# Main.net
KiCad netlist of a schematic drawn in Altium Designer
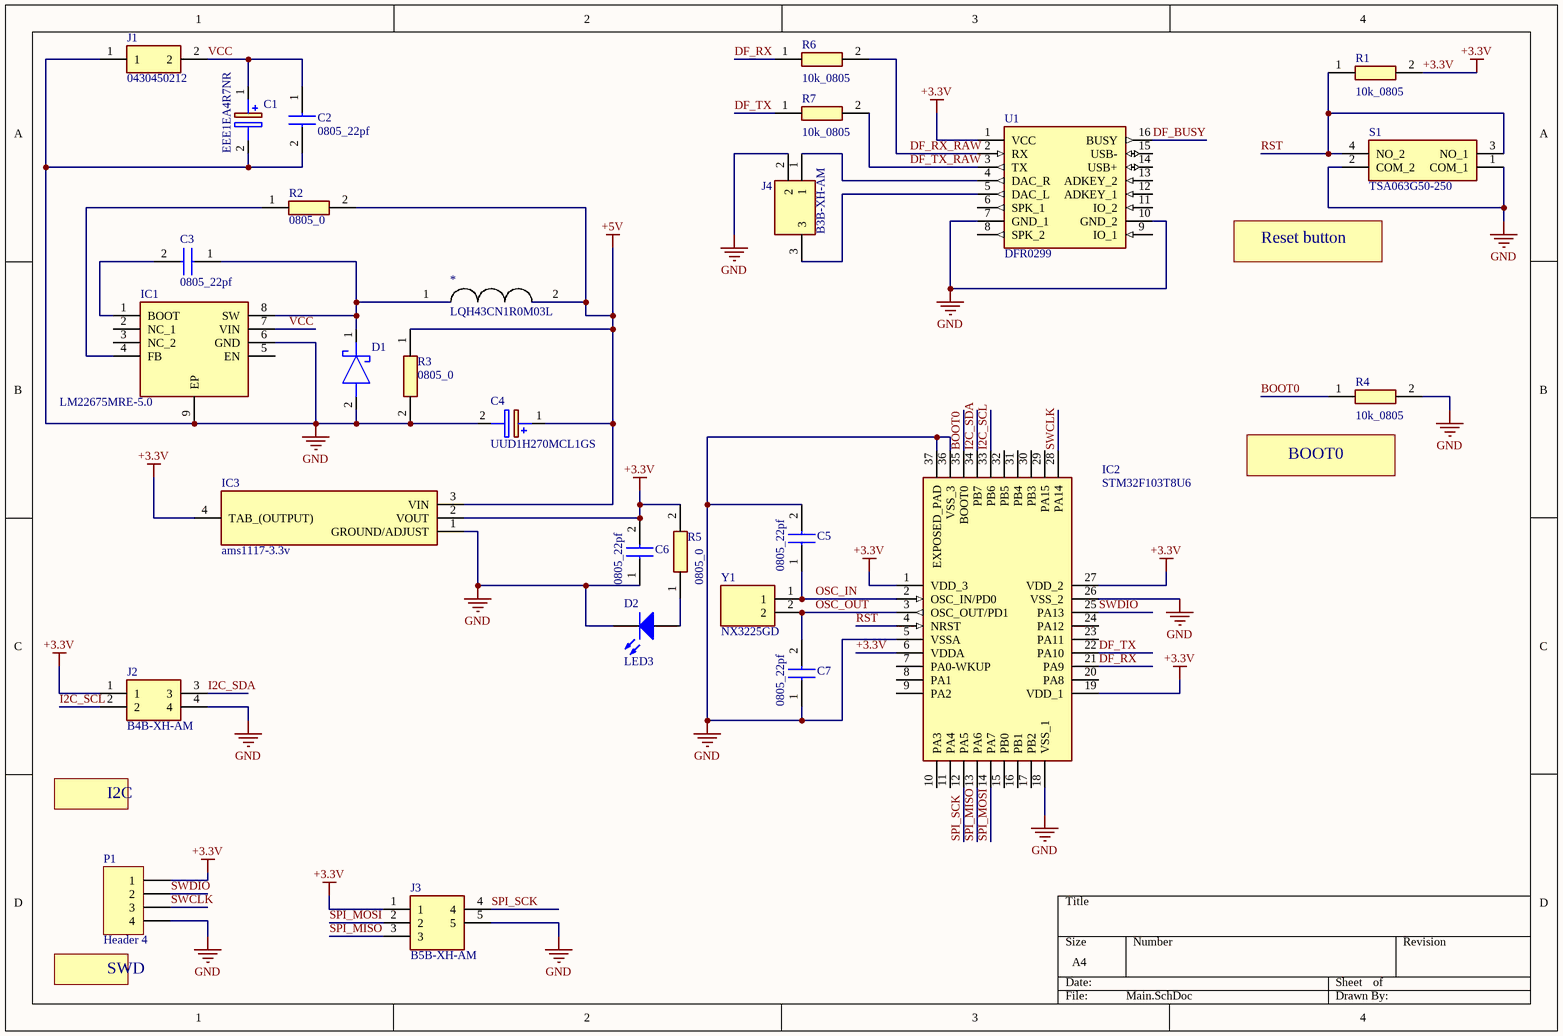
[diagram p0: Main.SchDoc]

(export (version "E")
  (design (tool "Eeschema 10.0.6"))
  (components
    (comp (ref "*")
      (value "LQH43CN1R0M03L")
      (footprint "*IND_LQH43CN1R0M03L")
      (libsource (lib "IND_LQH43CN1R0M03L") (part "Component_1"))
    )
    (comp (ref "C1")
      (value "EEE1EA4R7NR")
      (footprint "SamacSys:CAPAE530X550N")
      (description "Capacitor Polarised")
      (libsource (lib "*") (part "EEE1EA4R7NR"))
    )
    (comp (ref "C2")
      (value "0805_22pf")
      (footprint "SamacSys:CAPC2012X94N")
      (description "Capacitor")
      (fields
        (field (name "MANUFACTURER_PART_NUMBER") "08055A101JAT2A")
        (field (name "MOUSER PART NUMBER") "581-08055A101J")
      )
      (libsource (lib "*") (part "08055A101JAT2A"))
    )
    (comp (ref "C3")
      (value "0805_22pf")
      (footprint "SamacSys:CAPC2012X94N")
      (description "Capacitor")
      (fields
        (field (name "MANUFACTURER_PART_NUMBER") "08055A101JAT2A")
        (field (name "MOUSER PART NUMBER") "581-08055A101J")
      )
      (libsource (lib "*") (part "08055A101JAT2A"))
    )
    (comp (ref "C4")
      (value "UUD1H270MCL1GS")
      (footprint "SamacSys:CAPAE660X820N")
      (description "Capacitor Polarised")
      (fields (field (name "MOUSER PART NUMBER") "647-UUD1H270MCL"))
      (libsource (lib "*") (part "UUD1H270MCL1GS"))
    )
    (comp (ref "C5")
      (value "0805_22pf")
      (footprint "SamacSys:CAPC2012X94N")
      (description "Capacitor")
      (fields
        (field (name "MANUFACTURER_PART_NUMBER") "08055A101JAT2A")
        (field (name "MOUSER PART NUMBER") "581-08055A101J")
      )
      (libsource (lib "*") (part "08055A101JAT2A"))
    )
    (comp (ref "C6")
      (value "0805_22pf")
      (footprint "SamacSys:CAPC2012X94N")
      (description "Capacitor")
      (fields
        (field (name "MANUFACTURER_PART_NUMBER") "08055A101JAT2A")
        (field (name "MOUSER PART NUMBER") "581-08055A101J")
      )
      (libsource (lib "*") (part "08055A101JAT2A"))
    )
    (comp (ref "C7")
      (value "0805_22pf")
      (footprint "SamacSys:CAPC2012X94N")
      (description "Capacitor")
      (fields
        (field (name "MANUFACTURER_PART_NUMBER") "08055A101JAT2A")
        (field (name "MOUSER PART NUMBER") "581-08055A101J")
      )
      (libsource (lib "*") (part "08055A101JAT2A"))
    )
    (comp (ref "D1")
      (value "VS-30BQ015-M3_9AT")
      (footprint "SamacSys:DIOM7959X262N")
      (description "Schottky Diode")
      (fields
        (field (name "MANUFACTURER_PART_NUMBER") "VS-30BQ015-M3/9AT")
        (field (name "MOUSER PART NUMBER") "78-VS-30BQ015-M39AT")
      )
      (libsource (lib "*") (part "VS-30BQ015-M3_9AT"))
    )
    (comp (ref "D2")
      (value "LED3")
      (footprint "3.5X2.8X1.9")
      (description "Typical BLUE SiC LED")
      (fields (field (name "PUBLISHER") "Altium Limited"))
      (libsource (lib "Miscellaneous Devices") (part "LED3"))
    )
    (comp (ref "IC1")
      (value "LM22675MRE-5.0")
      (footprint "SamacSys:SOIC127P600X170-9N")
      (description "Integrated Circuit")
      (fields
        (field (name "MANUFACTURER_PART_NUMBER") "LM22675MRE-5.0/NOPB")
        (field (name "MOUSER PART NUMBER") "926-LM22675MRE50NOPB")
      )
      (libsource (lib "*") (part "LM22675MRE-5.0_NOPB"))
    )
    (comp (ref "IC2")
      (value "STM32F103T8U6")
      (footprint "Model Name")
      (description "Integrated Circuit")
      (fields
        (field (name "MOUSER PART NUMBER") "511-STM32F103T8U6")
        (field (name "RS PART NUMBER") "7249612P")
      )
      (libsource (lib "*") (part "STM32F103T8U6"))
    )
    (comp (ref "IC3")
      (value "ams1117-3.3v")
      (footprint "SamacSys:SOT229P700X180-4N")
      (description "Integrated Circuit")
      (libsource (lib "*") (part "ams1117-3.3v"))
    )
    (comp (ref "J1")
      (value "0430450212")
      (footprint "SamacSys:0430450212")
      (description "Connector")
      (libsource (lib "*") (part "0430450212"))
    )
    (comp (ref "J2")
      (value "B4B-XH-AM")
      (footprint "SamacSys:B4BXHAMLFSN")
      (description "Connector")
      (fields
        (field (name "MANUFACTURER_PART_NUMBER") "B4B-XH-AM (LF)(SN)")
        (field (name "RS PART NUMBER") "1755445")
      )
      (libsource (lib "*") (part "B4B-XH-AM_(LF)(SN)"))
    )
    (comp (ref "J3")
      (value "B5B-XH-AM")
      (footprint "SamacSys:B5BXHAMLFSN")
      (description "Connector")
      (fields
        (field (name "MANUFACTURER_PART_NUMBER") "B5B-XH-AM (LF)(SN)")
        (field (name "RS PART NUMBER") "1755489")
      )
      (libsource (lib "*") (part "B5B-XH-AM_(LF)(SN)"))
    )
    (comp (ref "J4")
      (value "B3B-XH-AM")
      (footprint "SamacSys:B3BXHAMLFSN")
      (description "Connector")
      (fields (field (name "MANUFACTURER_PART_NUMBER") "B3B-XH-AM(LF)(SN)"))
      (libsource (lib "*") (part "B3B-XH-AM(LF)(SN)"))
    )
    (comp (ref "P1")
      (value "Header 4")
      (footprint "HDR1X4")
      (description "Header, 4-Pin")
      (fields (field (name "PUBLISHER") "Altium Limited"))
      (libsource (lib "Miscellaneous Connectors") (part "Header 4"))
    )
    (comp (ref "R1")
      (value "10k_0805")
      (footprint "SamacSys:RESC2012X65N")
      (description "Resistor")
      (fields
        (field (name "MANUFACTURER_PART_NUMBER") "CPF0805B100KE")
        (field (name "MOUSER PART NUMBER") "279-CPF0805B100KE")
      )
      (libsource (lib "*") (part "CPF0805B100KE"))
    )
    (comp (ref "R2")
      (value "0805_0")
      (footprint "SamacSys:RESC2012X65N")
      (description "Resistor")
      (fields
        (field (name "MANUFACTURER_PART_NUMBER") "CPF0805B100KE")
        (field (name "MOUSER PART NUMBER") "279-CPF0805B100KE")
      )
      (libsource (lib "*") (part "CPF0805B100KE"))
    )
    (comp (ref "R3")
      (value "0805_0")
      (footprint "SamacSys:RESC2012X65N")
      (description "Resistor")
      (fields
        (field (name "MANUFACTURER_PART_NUMBER") "CPF0805B100KE")
        (field (name "MOUSER PART NUMBER") "279-CPF0805B100KE")
      )
      (libsource (lib "") (part "CPF0805B100KE_2"))
    )
    (comp (ref "R4")
      (value "10k_0805")
      (footprint "SamacSys:RESC2012X65N")
      (description "Resistor")
      (fields
        (field (name "MANUFACTURER_PART_NUMBER") "CPF0805B100KE")
        (field (name "MOUSER PART NUMBER") "279-CPF0805B100KE")
      )
      (libsource (lib "*") (part "CPF0805B100KE"))
    )
    (comp (ref "R5")
      (value "0805_0")
      (footprint "SamacSys:RESC2012X65N")
      (description "Resistor")
      (fields
        (field (name "MANUFACTURER_PART_NUMBER") "CPF0805B100KE")
        (field (name "MOUSER PART NUMBER") "279-CPF0805B100KE")
      )
      (libsource (lib "") (part "CPF0805B100KE_1"))
    )
    (comp (ref "R6")
      (value "10k_0805")
      (footprint "SamacSys:RESC2012X65N")
      (description "Resistor")
      (fields
        (field (name "MANUFACTURER_PART_NUMBER") "CPF0805B100KE")
        (field (name "MOUSER PART NUMBER") "279-CPF0805B100KE")
      )
      (libsource (lib "*") (part "CPF0805B100KE"))
    )
    (comp (ref "R7")
      (value "10k_0805")
      (footprint "SamacSys:RESC2012X65N")
      (description "Resistor")
      (fields
        (field (name "MANUFACTURER_PART_NUMBER") "CPF0805B100KE")
        (field (name "MOUSER PART NUMBER") "279-CPF0805B100KE")
      )
      (libsource (lib "*") (part "CPF0805B100KE"))
    )
    (comp (ref "S1")
      (value "TSA063G50-250")
      (footprint "SamacSys:TSA063G50250")
      (description "Switch")
      (libsource (lib "*") (part "TSA063G50-250"))
    )
    (comp (ref "U1")
      (value "DFR0299")
      (footprint "SamacSys:DIPS1778W50P254L2100H170Q16N")
      (description "Undefined or Miscellaneous")
      (fields (field (name "MOUSER PART NUMBER") "426-DFR0299"))
      (libsource (lib "*") (part "DFR0299"))
    )
    (comp (ref "Y1")
      (value "NX3225GD")
      (footprint "SamacSys:RESC3226X100N")
      (description "Crystal or Oscillator")
      (fields
        (field (name "MANUFACTURER_PART_NUMBER") "NX3225GD-8MHZ-STD-CRA-3")
        (field (name "MOUSER PART NUMBER") "344-NX3225GD8MCRA3")
      )
      (libsource (lib "*") (part "NX3225GD-8MHZ-STD-CRA-3"))
    )
  )
  (nets
    (net (code "1") (name "+3.3V") (class "Default")
      (node (ref "C6") (pin "2") (pinfunction "2_2") (pintype "passive"))
      (node (ref "IC2") (pin "1") (pinfunction "VDD_3_1") (pintype "power_in"))
      (node (ref "IC2") (pin "19") (pinfunction "VDD_1_19") (pintype "power_in"))
      (node (ref "IC2") (pin "27") (pinfunction "VDD_2_27") (pintype "power_in"))
      (node (ref "IC2") (pin "6") (pinfunction "VDDA_6") (pintype "power_in"))
      (node (ref "IC3") (pin "2") (pinfunction "VOUT_2") (pintype "passive"))
      (node (ref "IC3") (pin "4") (pinfunction "TAB_(OUTPUT)_4") (pintype "passive"))
      (node (ref "J2") (pin "1") (pinfunction "1_1") (pintype "passive"))
      (node (ref "J3") (pin "1") (pinfunction "1_1") (pintype "passive"))
      (node (ref "P1") (pin "1") (pinfunction "1_1") (pintype "passive"))
      (node (ref "R1") (pin "2") (pinfunction "2_2") (pintype "passive"))
      (node (ref "R5") (pin "2") (pinfunction "2_2") (pintype "passive"))
      (node (ref "U1") (pin "1") (pinfunction "VCC_1") (pintype "power_in"))
    )
    (net (code "2") (name "+5V") (class "Default")
      (node (ref "*") (pin "2") (pinfunction "2_2") (pintype "passive"))
      (node (ref "C4") (pin "1") (pinfunction "+_1") (pintype "passive"))
      (node (ref "IC3") (pin "3") (pinfunction "VIN_3") (pintype "passive"))
      (node (ref "R2") (pin "2") (pinfunction "2_2") (pintype "passive"))
      (node (ref "R3") (pin "1") (pinfunction "1_1") (pintype "passive"))
    )
    (net (code "3") (name "/BOOT0") (class "Default")
      (node (ref "IC2") (pin "35") (pinfunction "BOOT0_35") (pintype "passive"))
      (node (ref "R4") (pin "1") (pinfunction "1_1") (pintype "passive"))
    )
    (net (code "4") (name "/DF_BUSY") (class "Default")
      (node (ref "U1") (pin "16") (pinfunction "BUSY_16") (pintype "output"))
    )
    (net (code "5") (name "/DF_RX") (class "Default")
      (node (ref "IC2") (pin "21") (pinfunction "PA9_21") (pintype "passive"))
      (node (ref "R6") (pin "1") (pinfunction "1_1") (pintype "passive"))
    )
    (net (code "6") (name "/DF_RX_RAW") (class "Default")
      (node (ref "R6") (pin "2") (pinfunction "2_2") (pintype "passive"))
      (node (ref "U1") (pin "2") (pinfunction "RX_2") (pintype "input"))
    )
    (net (code "7") (name "/DF_TX") (class "Default")
      (node (ref "IC2") (pin "22") (pinfunction "PA10_22") (pintype "passive"))
      (node (ref "R7") (pin "1") (pinfunction "1_1") (pintype "passive"))
    )
    (net (code "8") (name "/DF_TX_RAW") (class "Default")
      (node (ref "R7") (pin "2") (pinfunction "2_2") (pintype "passive"))
      (node (ref "U1") (pin "3") (pinfunction "TX_3") (pintype "output"))
    )
    (net (code "9") (name "/I2C_SCL") (class "Default")
      (node (ref "IC2") (pin "33") (pinfunction "PB6_33") (pintype "passive"))
      (node (ref "J2") (pin "2") (pinfunction "2_2") (pintype "passive"))
    )
    (net (code "10") (name "/I2C_SDA") (class "Default")
      (node (ref "IC2") (pin "34") (pinfunction "PB7_34") (pintype "passive"))
      (node (ref "J2") (pin "3") (pinfunction "3_3") (pintype "passive"))
    )
    (net (code "11") (name "/OSC_IN") (class "Default")
      (node (ref "C5") (pin "1") (pinfunction "1_1") (pintype "passive"))
      (node (ref "IC2") (pin "2") (pinfunction "OSC_IN/PD0_2") (pintype "input"))
      (node (ref "Y1") (pin "1") (pinfunction "1_1") (pintype "passive"))
    )
    (net (code "12") (name "/OSC_OUT") (class "Default")
      (node (ref "C7") (pin "2") (pinfunction "2_2") (pintype "passive"))
      (node (ref "IC2") (pin "3") (pinfunction "OSC_OUT/PD1_3") (pintype "output"))
      (node (ref "Y1") (pin "2") (pinfunction "2_2") (pintype "passive"))
    )
    (net (code "13") (name "/RST") (class "Default")
      (node (ref "IC2") (pin "4") (pinfunction "NRST_4") (pintype "input"))
      (node (ref "R1") (pin "1") (pinfunction "1_1") (pintype "passive"))
      (node (ref "S1") (pin "3") (pinfunction "NO_1_3") (pintype "passive"))
      (node (ref "S1") (pin "4") (pinfunction "NO_2_4") (pintype "passive"))
    )
    (net (code "14") (name "/SPI_MISO") (class "Default")
      (node (ref "IC2") (pin "13") (pinfunction "PA6_13") (pintype "passive"))
      (node (ref "J3") (pin "3") (pinfunction "3_3") (pintype "passive"))
    )
    (net (code "15") (name "/SPI_MOSI") (class "Default")
      (node (ref "IC2") (pin "14") (pinfunction "PA7_14") (pintype "passive"))
      (node (ref "J3") (pin "2") (pinfunction "2_2") (pintype "passive"))
    )
    (net (code "16") (name "/SPI_SCK") (class "Default")
      (node (ref "IC2") (pin "12") (pinfunction "PA5_12") (pintype "passive"))
      (node (ref "J3") (pin "4") (pinfunction "4_4") (pintype "passive"))
    )
    (net (code "17") (name "/SWCLK") (class "Default")
      (node (ref "IC2") (pin "28") (pinfunction "PA14_28") (pintype "passive"))
      (node (ref "P1") (pin "3") (pinfunction "3_3") (pintype "passive"))
    )
    (net (code "18") (name "/SWDIO") (class "Default")
      (node (ref "IC2") (pin "25") (pinfunction "PA13_25") (pintype "passive"))
      (node (ref "P1") (pin "2") (pinfunction "2_2") (pintype "passive"))
    )
    (net (code "19") (name "/VCC") (class "Default")
      (node (ref "C1") (pin "1") (pinfunction "+_1") (pintype "passive"))
      (node (ref "C2") (pin "1") (pinfunction "1_1") (pintype "passive"))
      (node (ref "IC1") (pin "7") (pinfunction "VIN_7") (pintype "passive"))
      (node (ref "J1") (pin "2") (pinfunction "2_2") (pintype "passive"))
    )
    (net (code "20") (name "GND") (class "Default")
      (node (ref "C1") (pin "2") (pinfunction "-_2") (pintype "passive"))
      (node (ref "C2") (pin "2") (pinfunction "2_2") (pintype "passive"))
      (node (ref "C4") (pin "2") (pinfunction "-_2") (pintype "passive"))
      (node (ref "C5") (pin "2") (pinfunction "2_2") (pintype "passive"))
      (node (ref "C6") (pin "1") (pinfunction "1_1") (pintype "passive"))
      (node (ref "C7") (pin "1") (pinfunction "1_1") (pintype "passive"))
      (node (ref "D1") (pin "2") (pinfunction "A_2") (pintype "passive"))
      (node (ref "D2") (pin "2") (pinfunction "K_2") (pintype "passive"))
      (node (ref "IC1") (pin "6") (pinfunction "GND_6") (pintype "passive"))
      (node (ref "IC1") (pin "9") (pinfunction "EP_9") (pintype "passive"))
      (node (ref "IC2") (pin "18") (pinfunction "VSS_1_18") (pintype "power_in"))
      (node (ref "IC2") (pin "26") (pinfunction "VSS_2_26") (pintype "power_in"))
      (node (ref "IC2") (pin "36") (pinfunction "VSS_3_36") (pintype "power_in"))
      (node (ref "IC2") (pin "37") (pinfunction "EXPOSED_PAD_37") (pintype "passive"))
      (node (ref "IC2") (pin "5") (pinfunction "VSSA_5") (pintype "power_in"))
      (node (ref "IC3") (pin "1") (pinfunction "GROUND/ADJUST_1") (pintype "passive"))
      (node (ref "J1") (pin "1") (pinfunction "1_1") (pintype "passive"))
      (node (ref "J2") (pin "4") (pinfunction "4_4") (pintype "passive"))
      (node (ref "J3") (pin "5") (pinfunction "5_5") (pintype "passive"))
      (node (ref "J4") (pin "2") (pinfunction "2_2") (pintype "passive"))
      (node (ref "P1") (pin "4") (pinfunction "4_4") (pintype "passive"))
      (node (ref "R3") (pin "2") (pinfunction "2_2") (pintype "passive"))
      (node (ref "R4") (pin "2") (pinfunction "2_2") (pintype "passive"))
      (node (ref "S1") (pin "1") (pinfunction "COM_1_1") (pintype "passive"))
      (node (ref "S1") (pin "2") (pinfunction "COM_2_2") (pintype "passive"))
      (node (ref "U1") (pin "10") (pinfunction "GND_2_10") (pintype "power_in"))
      (node (ref "U1") (pin "7") (pinfunction "GND_1_7") (pintype "power_in"))
    )
    (net (code "21") (name "Net-(D1-K)") (class "Default")
      (node (ref "*") (pin "1") (pinfunction "1_1") (pintype "passive"))
      (node (ref "C3") (pin "1") (pinfunction "1_1") (pintype "passive"))
      (node (ref "D1") (pin "1") (pinfunction "K_1") (pintype "passive"))
      (node (ref "IC1") (pin "8") (pinfunction "SW_8") (pintype "passive"))
    )
    (net (code "22") (name "Net-(D2-A)") (class "Default")
      (node (ref "D2") (pin "1") (pinfunction "A_1") (pintype "passive"))
      (node (ref "R5") (pin "1") (pinfunction "1_1") (pintype "passive"))
    )
    (net (code "23") (name "Net-(IC1-BOOT)") (class "Default")
      (node (ref "C3") (pin "2") (pinfunction "2_2") (pintype "passive"))
      (node (ref "IC1") (pin "1") (pinfunction "BOOT_1") (pintype "passive"))
    )
    (net (code "24") (name "Net-(IC1-FB)") (class "Default")
      (node (ref "IC1") (pin "4") (pinfunction "FB_4") (pintype "passive"))
      (node (ref "R2") (pin "1") (pinfunction "1_1") (pintype "passive"))
    )
    (net (code "25") (name "Net-(U1-DAC_L)") (class "Default")
      (node (ref "J4") (pin "3") (pinfunction "3_3") (pintype "passive"))
      (node (ref "U1") (pin "5") (pinfunction "DAC_L_5") (pintype "output"))
    )
    (net (code "26") (name "Net-(U1-DAC_R)") (class "Default")
      (node (ref "J4") (pin "1") (pinfunction "1_1") (pintype "passive"))
      (node (ref "U1") (pin "4") (pinfunction "DAC_R_4") (pintype "output"))
    )
    (net (code "27") (name "unconnected-(IC1-EN-Pad5)") (class "Default")
      (node (ref "IC1") (pin "5") (pinfunction "EN_5") (pintype "passive"))
    )
    (net (code "28") (name "unconnected-(IC1-NC_1-Pad2)") (class "Default")
      (node (ref "IC1") (pin "2") (pinfunction "NC_1_2") (pintype "passive"))
    )
    (net (code "29") (name "unconnected-(IC1-NC_2-Pad3)") (class "Default")
      (node (ref "IC1") (pin "3") (pinfunction "NC_2_3") (pintype "passive"))
    )
    (net (code "30") (name "unconnected-(IC2-PA0-WKUP-Pad7)") (class "Default")
      (node (ref "IC2") (pin "7") (pinfunction "PA0-WKUP_7") (pintype "passive"))
    )
    (net (code "31") (name "unconnected-(IC2-PA1-Pad8)") (class "Default")
      (node (ref "IC2") (pin "8") (pinfunction "PA1_8") (pintype "passive"))
    )
    (net (code "32") (name "unconnected-(IC2-PA2-Pad9)") (class "Default")
      (node (ref "IC2") (pin "9") (pinfunction "PA2_9") (pintype "passive"))
    )
    (net (code "33") (name "unconnected-(IC2-PA3-Pad10)") (class "Default")
      (node (ref "IC2") (pin "10") (pinfunction "PA3_10") (pintype "passive"))
    )
    (net (code "34") (name "unconnected-(IC2-PA4-Pad11)") (class "Default")
      (node (ref "IC2") (pin "11") (pinfunction "PA4_11") (pintype "passive"))
    )
    (net (code "35") (name "unconnected-(IC2-PA8-Pad20)") (class "Default")
      (node (ref "IC2") (pin "20") (pinfunction "PA8_20") (pintype "passive"))
    )
    (net (code "36") (name "unconnected-(IC2-PA11-Pad23)") (class "Default")
      (node (ref "IC2") (pin "23") (pinfunction "PA11_23") (pintype "passive"))
    )
    (net (code "37") (name "unconnected-(IC2-PA12-Pad24)") (class "Default")
      (node (ref "IC2") (pin "24") (pinfunction "PA12_24") (pintype "passive"))
    )
    (net (code "38") (name "unconnected-(IC2-PA15-Pad29)") (class "Default")
      (node (ref "IC2") (pin "29") (pinfunction "PA15_29") (pintype "passive"))
    )
    (net (code "39") (name "unconnected-(IC2-PB0-Pad15)") (class "Default")
      (node (ref "IC2") (pin "15") (pinfunction "PB0_15") (pintype "passive"))
    )
    (net (code "40") (name "unconnected-(IC2-PB1-Pad16)") (class "Default")
      (node (ref "IC2") (pin "16") (pinfunction "PB1_16") (pintype "passive"))
    )
    (net (code "41") (name "unconnected-(IC2-PB2-Pad17)") (class "Default")
      (node (ref "IC2") (pin "17") (pinfunction "PB2_17") (pintype "passive"))
    )
    (net (code "42") (name "unconnected-(IC2-PB3-Pad30)") (class "Default")
      (node (ref "IC2") (pin "30") (pinfunction "PB3_30") (pintype "passive"))
    )
    (net (code "43") (name "unconnected-(IC2-PB4-Pad31)") (class "Default")
      (node (ref "IC2") (pin "31") (pinfunction "PB4_31") (pintype "passive"))
    )
    (net (code "44") (name "unconnected-(IC2-PB5-Pad32)") (class "Default")
      (node (ref "IC2") (pin "32") (pinfunction "PB5_32") (pintype "passive"))
    )
    (net (code "45") (name "unconnected-(U1-ADKEY_1-Pad12)") (class "Default")
      (node (ref "U1") (pin "12") (pinfunction "ADKEY_1_12") (pintype "input"))
    )
    (net (code "46") (name "unconnected-(U1-ADKEY_2-Pad13)") (class "Default")
      (node (ref "U1") (pin "13") (pinfunction "ADKEY_2_13") (pintype "input"))
    )
    (net (code "47") (name "unconnected-(U1-IO_1-Pad9)") (class "Default")
      (node (ref "U1") (pin "9") (pinfunction "IO_1_9") (pintype "input"))
    )
    (net (code "48") (name "unconnected-(U1-IO_2-Pad11)") (class "Default")
      (node (ref "U1") (pin "11") (pinfunction "IO_2_11") (pintype "input"))
    )
    (net (code "49") (name "unconnected-(U1-SPK_1-Pad6)") (class "Default")
      (node (ref "U1") (pin "6") (pinfunction "SPK_1_6") (pintype "output"))
    )
    (net (code "50") (name "unconnected-(U1-SPK_2-Pad8)") (class "Default")
      (node (ref "U1") (pin "8") (pinfunction "SPK_2_8") (pintype "output"))
    )
    (net (code "51") (name "unconnected-(U1-USB+-Pad14)") (class "Default")
      (node (ref "U1") (pin "14") (pinfunction "USB+_14") (pintype "bidirectional"))
    )
    (net (code "52") (name "unconnected-(U1-USB--Pad15)") (class "Default")
      (node (ref "U1") (pin "15") (pinfunction "USB-_15") (pintype "bidirectional"))
    )
  )
)
